# SAMD21_16X10_V2_schematic.net
KiCad netlist of a schematic drawn in Altium Designer
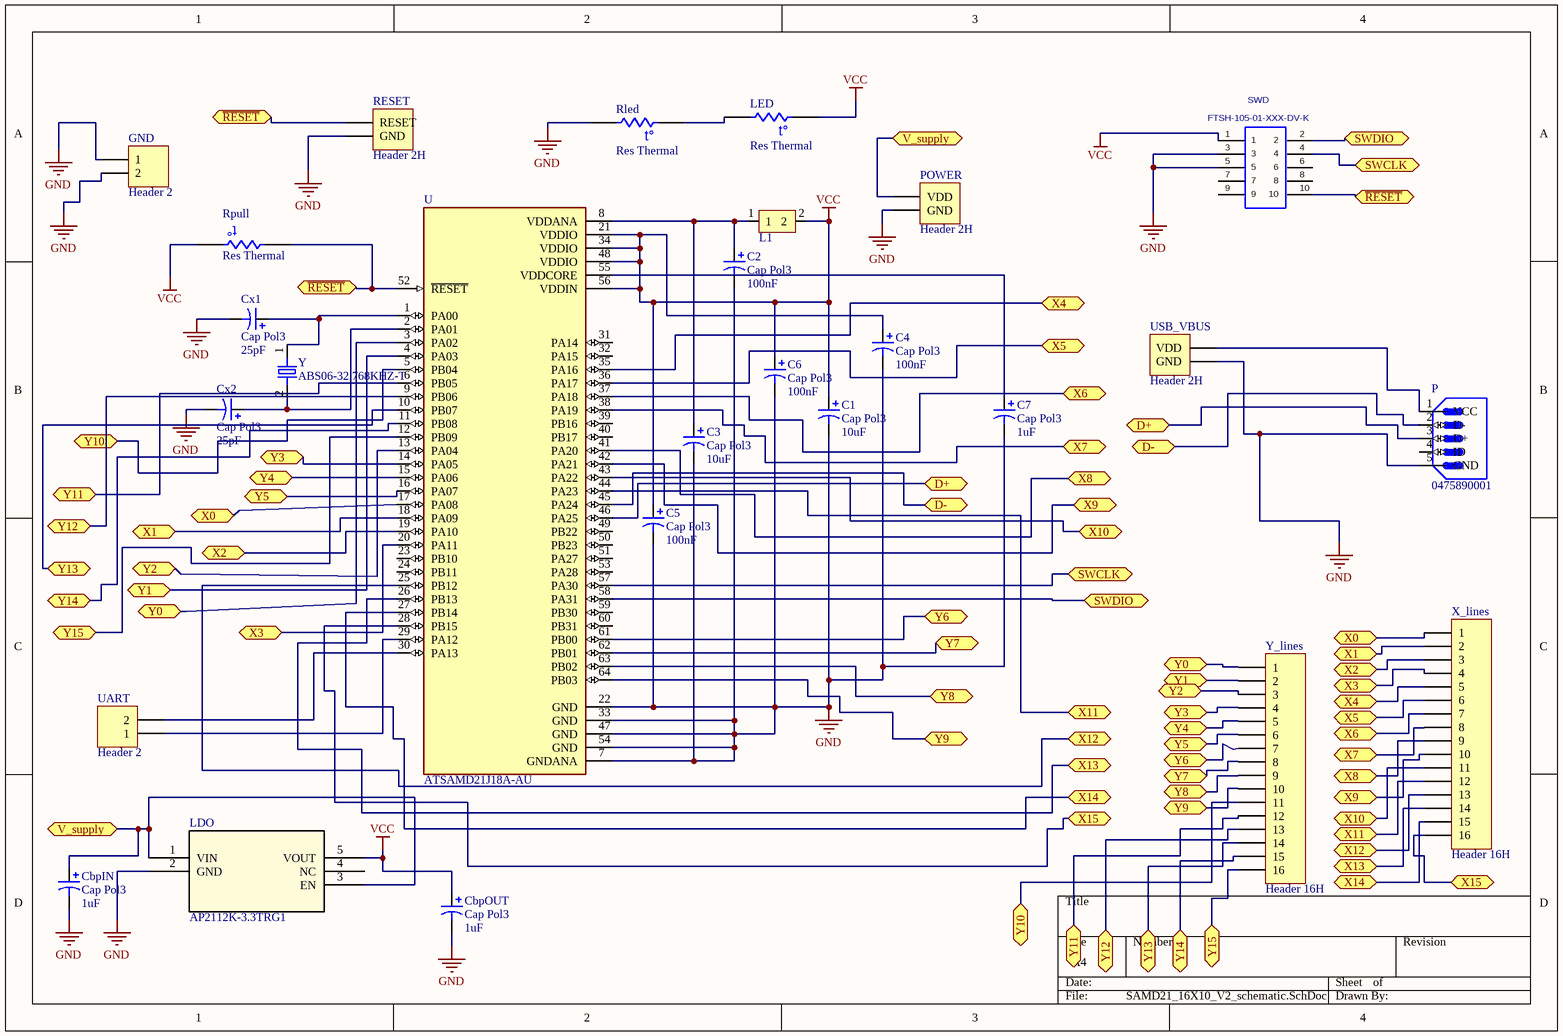
[diagram p0: SAMD21_16X10_V2_schematic.SchDoc]

(export (version "E")
  (design (tool "Eeschema 10.0.6"))
  (components
    (comp (ref "C1")
      (value "Cap Pol3")
      (footprint "C0805")
      (description "Polarized Capacitor (Surface Mount)")
      (fields (field (name "ALTIUM_VALUE") "10uF") (field (name "PUBLISHER") "Altium Limited"))
      (libsource (lib "Miscellaneous Devices") (part "Cap Pol3"))
    )
    (comp (ref "C2")
      (value "Cap Pol3")
      (footprint "C0805")
      (description "Polarized Capacitor (Surface Mount)")
      (fields (field (name "ALTIUM_VALUE") "100nF") (field (name "PUBLISHER") "Altium Limited"))
      (libsource (lib "Miscellaneous Devices") (part "Cap Pol3"))
    )
    (comp (ref "C3")
      (value "Cap Pol3")
      (footprint "C0805")
      (description "Polarized Capacitor (Surface Mount)")
      (fields (field (name "ALTIUM_VALUE") "10uF") (field (name "PUBLISHER") "Altium Limited"))
      (libsource (lib "Miscellaneous Devices") (part "Cap Pol3"))
    )
    (comp (ref "C4")
      (value "Cap Pol3")
      (footprint "C0805")
      (description "Polarized Capacitor (Surface Mount)")
      (fields (field (name "ALTIUM_VALUE") "100nF") (field (name "PUBLISHER") "Altium Limited"))
      (libsource (lib "Miscellaneous Devices") (part "Cap Pol3"))
    )
    (comp (ref "C5")
      (value "Cap Pol3")
      (footprint "C0805")
      (description "Polarized Capacitor (Surface Mount)")
      (fields (field (name "ALTIUM_VALUE") "100nF") (field (name "PUBLISHER") "Altium Limited"))
      (libsource (lib "Miscellaneous Devices") (part "Cap Pol3"))
    )
    (comp (ref "C6")
      (value "Cap Pol3")
      (footprint "C0805")
      (description "Polarized Capacitor (Surface Mount)")
      (fields (field (name "ALTIUM_VALUE") "100nF") (field (name "PUBLISHER") "Altium Limited"))
      (libsource (lib "Miscellaneous Devices") (part "Cap Pol3"))
    )
    (comp (ref "C7")
      (value "Cap Pol3")
      (footprint "C0805")
      (description "Polarized Capacitor (Surface Mount)")
      (fields (field (name "ALTIUM_VALUE") "1uF") (field (name "PUBLISHER") "Altium Limited"))
      (libsource (lib "Miscellaneous Devices") (part "Cap Pol3"))
    )
    (comp (ref "CbpIN")
      (value "Cap Pol3")
      (footprint "C0805")
      (description "Polarized Capacitor (Surface Mount)")
      (fields (field (name "ALTIUM_VALUE") "1uF") (field (name "PUBLISHER") "Altium Limited"))
      (libsource (lib "Miscellaneous Devices") (part "Cap Pol3"))
    )
    (comp (ref "CbpOUT")
      (value "Cap Pol3")
      (footprint "C0805")
      (description "Polarized Capacitor (Surface Mount)")
      (fields (field (name "ALTIUM_VALUE") "1uF") (field (name "PUBLISHER") "Altium Limited"))
      (libsource (lib "Miscellaneous Devices") (part "Cap Pol3"))
    )
    (comp (ref "Cx1")
      (value "Cap Pol3")
      (footprint "C0805")
      (description "Polarized Capacitor (Surface Mount)")
      (fields (field (name "ALTIUM_VALUE") "25pF") (field (name "PUBLISHER") "Altium Limited"))
      (libsource (lib "Miscellaneous Devices") (part "Cap Pol3"))
    )
    (comp (ref "Cx2")
      (value "Cap Pol3")
      (footprint "C0805")
      (description "Polarized Capacitor (Surface Mount)")
      (fields (field (name "ALTIUM_VALUE") "25pF") (field (name "PUBLISHER") "Altium Limited"))
      (libsource (lib "Miscellaneous Devices") (part "Cap Pol3"))
    )
    (comp (ref "GND")
      (value "Header 2")
      (footprint "HDR1X2")
      (description "Header, 2-Pin")
      (fields (field (name "PUBLISHER") "Altium Limited"))
      (libsource (lib "Miscellaneous Connectors") (part "Header 2"))
    )
    (comp (ref "L1")
      (value "SRP4012TA-100M")
      (footprint "Inductor")
      (description "Inductor")
      (libsource (lib "SRP4012TA") (part "SRP4012TA-100M"))
    )
    (comp (ref "LDO")
      (value "AP2112K-3.3TRG1")
      (footprint "SOT_RG1_DIO")
      (description "No Description Available")
      (fields (field (name "COPYRIGHT") "Copyright (C) 2018 Accelerated Designs. All rights reserved"))
      (libsource (lib "2020-09-03_20-14-04") (part "AP2112K-3.3TRG1"))
    )
    (comp (ref "LED")
      (value "Res Thermal")
      (footprint "6-0805_N")
      (description "Thermistor")
      (fields (field (name "PUBLISHER") "Altium Limited"))
      (libsource (lib "Miscellaneous Devices") (part "Res Thermal"))
    )
    (comp (ref "P")
      (value "0475890001")
      (footprint "MOLEX_0475890001")
      (description "USB - micro AB Receptacle Connector 5 Position Surface Mount, Right Angle; Through Hole")
      (fields (field (name "DIGI-KEY_PART_NUMBER") "WM17143CT-ND") (field (name "MF") "Molex"))
      (libsource (lib "0475890001") (part "0475890001"))
    )
    (comp (ref "POWER")
      (value "Header 2H")
      (footprint "HDR1X2H")
      (description "Header, 2-Pin, Right Angle")
      (fields (field (name "PUBLISHER") "Altium Limited"))
      (libsource (lib "") (part "Header 2H_1"))
    )
    (comp (ref "RESET")
      (value "Header 2H")
      (footprint "HDR1X2H")
      (description "Header, 2-Pin, Right Angle")
      (fields (field (name "PUBLISHER") "Altium Limited"))
      (libsource (lib "") (part "Header 2H_1"))
    )
    (comp (ref "Rled")
      (value "Res Thermal")
      (footprint "6-0805_N")
      (description "Thermistor")
      (fields (field (name "PUBLISHER") "Altium Limited"))
      (libsource (lib "Miscellaneous Devices") (part "Res Thermal"))
    )
    (comp (ref "Rpull")
      (value "Res Thermal")
      (footprint "6-0805_N")
      (description "Thermistor")
      (fields (field (name "PUBLISHER") "Altium Limited"))
      (libsource (lib "Miscellaneous Devices") (part "Res Thermal"))
    )
    (comp (ref "SWD")
      (value "FTSH-105-01-XXX-DV-K")
      (footprint "FTSH-105-01-XXX-DV-K")
      (description "TERMINAL STRIP, .050\"(1.27mm) PITCH, 10 PINS, KEYED")
      (fields (field (name "MANUFACTURER") "SAMTEC") (field (name "CREATED") "November 30, 2016 - Wendy Xin"))
      (libsource (lib "FTSH-105-01-XXX-DV-K--Symbol-Altium-44987") (part "FTSH-105-01-XXX-DV-K"))
    )
    (comp (ref "U")
      (value "ATSAMD21J18A-AU")
      (footprint "QFP80P1600X1600X120-64N")
      (description "ARMÂ® CortexÂ®-M0+ SAM D21J Microcontroller IC 32-Bit 48MHz 256KB _256K x 8_ FLASH 64-TQFP _10x10_")
      (fields (field (name "MF") "Microchip"))
      (libsource (lib "ATSAMD21J18A-AU") (part "ATSAMD21J18A-AU"))
    )
    (comp (ref "UART")
      (value "Header 2")
      (footprint "HDR1X2")
      (description "Header, 2-Pin")
      (fields (field (name "PUBLISHER") "Altium Limited"))
      (libsource (lib "") (part "Header 2_1"))
    )
    (comp (ref "USB_VBUS")
      (value "Header 2H")
      (footprint "HDR1X2H")
      (description "Header, 2-Pin, Right Angle")
      (fields (field (name "PUBLISHER") "Altium Limited"))
      (libsource (lib "Miscellaneous Connectors") (part "Header 2H"))
    )
    (comp (ref "X_lines")
      (value "Header 16H")
      (footprint "HDR1X16H")
      (description "Header, 16-Pin, Right Angle")
      (fields (field (name "PUBLISHER") "Altium Limited"))
      (libsource (lib "Miscellaneous Connectors") (part "Header 16H"))
    )
    (comp (ref "Y")
      (value "ABS06-32.768KHZ-T")
      (footprint "XTAL_ABS06-32.768KHZ-T")
      (description "32.768kHz Â±20ppm Crystal 12.5pF 90 kOhms 2-SMD, No Lead")
      (fields (field (name "MF") "Abracon"))
      (libsource (lib "ABS06-32.768KHZ-T") (part "ABS06-32.768KHZ-T"))
    )
    (comp (ref "Y_lines")
      (value "Header 16H")
      (footprint "HDR1X16H")
      (description "Header, 16-Pin, Right Angle")
      (fields (field (name "PUBLISHER") "Altium Limited"))
      (libsource (lib "Miscellaneous Connectors") (part "Header 16H"))
    )
  )
  (nets
    (net (code "1") (name "/D+") (class "Default")
      (node (ref "P") (pin "3") (pinfunction "D+_3") (pintype "bidirectional"))
      (node (ref "U") (pin "46") (pinfunction "PA25_46") (pintype "bidirectional"))
    )
    (net (code "2") (name "/D-") (class "Default")
      (node (ref "P") (pin "2") (pinfunction "D-_2") (pintype "bidirectional"))
      (node (ref "U") (pin "45") (pinfunction "PA24_45") (pintype "bidirectional"))
    )
    (net (code "3") (name "/SWCLK") (class "Default")
      (node (ref "SWD") (pin "4") (pinfunction "4_4") (pintype "passive"))
      (node (ref "U") (pin "57") (pinfunction "PA30_57") (pintype "bidirectional"))
    )
    (net (code "4") (name "/SWDIO") (class "Default")
      (node (ref "SWD") (pin "2") (pinfunction "2_2") (pintype "passive"))
      (node (ref "U") (pin "58") (pinfunction "PA31_58") (pintype "bidirectional"))
    )
    (net (code "5") (name "/V_supply") (class "Default")
      (node (ref "CbpIN") (pin "1") (pinfunction "1_1") (pintype "passive"))
      (node (ref "LDO") (pin "1") (pinfunction "VIN_1") (pintype "passive"))
      (node (ref "LDO") (pin "3") (pinfunction "EN_3") (pintype "passive"))
      (node (ref "POWER") (pin "1") (pinfunction "RESET_1") (pintype "passive"))
    )
    (net (code "6") (name "/X0") (class "Default")
      (node (ref "U") (pin "17") (pinfunction "PA08_17") (pintype "bidirectional"))
      (node (ref "X_lines") (pin "1") (pinfunction "1_1") (pintype "passive"))
    )
    (net (code "7") (name "/X1") (class "Default")
      (node (ref "U") (pin "18") (pinfunction "PA09_18") (pintype "bidirectional"))
      (node (ref "X_lines") (pin "2") (pinfunction "2_2") (pintype "passive"))
    )
    (net (code "8") (name "/X2") (class "Default")
      (node (ref "U") (pin "19") (pinfunction "PA10_19") (pintype "bidirectional"))
      (node (ref "X_lines") (pin "3") (pinfunction "3_3") (pintype "passive"))
    )
    (net (code "9") (name "/X3") (class "Default")
      (node (ref "U") (pin "20") (pinfunction "PA11_20") (pintype "bidirectional"))
      (node (ref "X_lines") (pin "4") (pinfunction "4_4") (pintype "passive"))
    )
    (net (code "10") (name "/X4") (class "Default")
      (node (ref "U") (pin "35") (pinfunction "PA16_35") (pintype "bidirectional"))
      (node (ref "X_lines") (pin "5") (pinfunction "5_5") (pintype "passive"))
    )
    (net (code "11") (name "/X5") (class "Default")
      (node (ref "U") (pin "36") (pinfunction "PA17_36") (pintype "bidirectional"))
      (node (ref "X_lines") (pin "6") (pinfunction "6_6") (pintype "passive"))
    )
    (net (code "12") (name "/X6") (class "Default")
      (node (ref "U") (pin "37") (pinfunction "PA18_37") (pintype "bidirectional"))
      (node (ref "X_lines") (pin "7") (pinfunction "7_7") (pintype "passive"))
    )
    (net (code "13") (name "/X7") (class "Default")
      (node (ref "U") (pin "38") (pinfunction "PA19_38") (pintype "bidirectional"))
      (node (ref "X_lines") (pin "8") (pinfunction "8_8") (pintype "passive"))
    )
    (net (code "14") (name "/X8") (class "Default")
      (node (ref "U") (pin "41") (pinfunction "PA20_41") (pintype "bidirectional"))
      (node (ref "X_lines") (pin "9") (pinfunction "9_9") (pintype "passive"))
    )
    (net (code "15") (name "/X9") (class "Default")
      (node (ref "U") (pin "42") (pinfunction "PA21_42") (pintype "bidirectional"))
      (node (ref "X_lines") (pin "10") (pinfunction "10_10") (pintype "passive"))
    )
    (net (code "16") (name "/X10") (class "Default")
      (node (ref "U") (pin "43") (pinfunction "PA22_43") (pintype "bidirectional"))
      (node (ref "X_lines") (pin "11") (pinfunction "11_11") (pintype "passive"))
    )
    (net (code "17") (name "/X11") (class "Default")
      (node (ref "U") (pin "44") (pinfunction "PA23_44") (pintype "bidirectional"))
      (node (ref "X_lines") (pin "12") (pinfunction "12_12") (pintype "passive"))
    )
    (net (code "18") (name "/X12") (class "Default")
      (node (ref "U") (pin "25") (pinfunction "PB12_25") (pintype "bidirectional"))
      (node (ref "X_lines") (pin "13") (pinfunction "13_13") (pintype "passive"))
    )
    (net (code "19") (name "/X13") (class "Default")
      (node (ref "U") (pin "26") (pinfunction "PB13_26") (pintype "bidirectional"))
      (node (ref "X_lines") (pin "14") (pinfunction "14_14") (pintype "passive"))
    )
    (net (code "20") (name "/X14") (class "Default")
      (node (ref "U") (pin "27") (pinfunction "PB14_27") (pintype "bidirectional"))
      (node (ref "X_lines") (pin "15") (pinfunction "15_15") (pintype "passive"))
    )
    (net (code "21") (name "/X15") (class "Default")
      (node (ref "U") (pin "28") (pinfunction "PB15_28") (pintype "bidirectional"))
      (node (ref "X_lines") (pin "16") (pinfunction "16_16") (pintype "passive"))
    )
    (net (code "22") (name "/Y0") (class "Default")
      (node (ref "U") (pin "3") (pinfunction "PA02_3") (pintype "bidirectional"))
      (node (ref "Y_lines") (pin "1") (pinfunction "1_1") (pintype "passive"))
    )
    (net (code "23") (name "/Y1") (class "Default")
      (node (ref "U") (pin "4") (pinfunction "PA03_4") (pintype "bidirectional"))
      (node (ref "Y_lines") (pin "2") (pinfunction "2_2") (pintype "passive"))
    )
    (net (code "24") (name "/Y2") (class "Default")
      (node (ref "U") (pin "13") (pinfunction "PA04_13") (pintype "bidirectional"))
      (node (ref "Y_lines") (pin "3") (pinfunction "3_3") (pintype "passive"))
    )
    (net (code "25") (name "/Y3") (class "Default")
      (node (ref "U") (pin "14") (pinfunction "PA05_14") (pintype "bidirectional"))
      (node (ref "Y_lines") (pin "4") (pinfunction "4_4") (pintype "passive"))
    )
    (net (code "26") (name "/Y4") (class "Default")
      (node (ref "U") (pin "15") (pinfunction "PA06_15") (pintype "bidirectional"))
      (node (ref "Y_lines") (pin "5") (pinfunction "5_5") (pintype "passive"))
    )
    (net (code "27") (name "/Y5") (class "Default")
      (node (ref "U") (pin "16") (pinfunction "PA07_16") (pintype "bidirectional"))
      (node (ref "Y_lines") (pin "6") (pinfunction "6_6") (pintype "passive"))
    )
    (net (code "28") (name "/Y6") (class "Default")
      (node (ref "U") (pin "61") (pinfunction "PB00_61") (pintype "bidirectional"))
      (node (ref "Y_lines") (pin "7") (pinfunction "7_7") (pintype "passive"))
    )
    (net (code "29") (name "/Y7") (class "Default")
      (node (ref "U") (pin "62") (pinfunction "PB01_62") (pintype "bidirectional"))
      (node (ref "Y_lines") (pin "8") (pinfunction "8_8") (pintype "passive"))
    )
    (net (code "30") (name "/Y8") (class "Default")
      (node (ref "U") (pin "63") (pinfunction "PB02_63") (pintype "bidirectional"))
      (node (ref "Y_lines") (pin "9") (pinfunction "9_9") (pintype "passive"))
    )
    (net (code "31") (name "/Y9") (class "Default")
      (node (ref "U") (pin "64") (pinfunction "PB03_64") (pintype "bidirectional"))
      (node (ref "Y_lines") (pin "10") (pinfunction "10_10") (pintype "passive"))
    )
    (net (code "32") (name "/Y10") (class "Default")
      (node (ref "U") (pin "5") (pinfunction "PB04_5") (pintype "bidirectional"))
      (node (ref "Y_lines") (pin "11") (pinfunction "11_11") (pintype "passive"))
    )
    (net (code "33") (name "/Y11") (class "Default")
      (node (ref "U") (pin "6") (pinfunction "PB05_6") (pintype "bidirectional"))
      (node (ref "Y_lines") (pin "12") (pinfunction "12_12") (pintype "passive"))
    )
    (net (code "34") (name "/Y12") (class "Default")
      (node (ref "U") (pin "9") (pinfunction "PB06_9") (pintype "bidirectional"))
      (node (ref "Y_lines") (pin "13") (pinfunction "13_13") (pintype "passive"))
    )
    (net (code "35") (name "/Y13") (class "Default")
      (node (ref "U") (pin "10") (pinfunction "PB07_10") (pintype "bidirectional"))
      (node (ref "Y_lines") (pin "14") (pinfunction "14_14") (pintype "passive"))
    )
    (net (code "36") (name "/Y14") (class "Default")
      (node (ref "U") (pin "11") (pinfunction "PB08_11") (pintype "bidirectional"))
      (node (ref "Y_lines") (pin "15") (pinfunction "15_15") (pintype "passive"))
    )
    (net (code "37") (name "/Y15") (class "Default")
      (node (ref "U") (pin "12") (pinfunction "PB09_12") (pintype "bidirectional"))
      (node (ref "Y_lines") (pin "16") (pinfunction "16_16") (pintype "passive"))
    )
    (net (code "38") (name "/~{RESET}") (class "Default")
      (node (ref "RESET") (pin "1") (pinfunction "RESET_1") (pintype "passive"))
      (node (ref "Rpull") (pin "2") (pinfunction "2_2") (pintype "passive"))
      (node (ref "SWD") (pin "10") (pinfunction "10_10") (pintype "passive"))
      (node (ref "U") (pin "52") (pinfunction "~{RESET}_52") (pintype "input"))
    )
    (net (code "39") (name "GND") (class "Default")
      (node (ref "C1") (pin "2") (pinfunction "2_2") (pintype "passive"))
      (node (ref "C2") (pin "2") (pinfunction "2_2") (pintype "passive"))
      (node (ref "C3") (pin "2") (pinfunction "2_2") (pintype "passive"))
      (node (ref "C4") (pin "2") (pinfunction "2_2") (pintype "passive"))
      (node (ref "C5") (pin "2") (pinfunction "2_2") (pintype "passive"))
      (node (ref "C6") (pin "2") (pinfunction "2_2") (pintype "passive"))
      (node (ref "C7") (pin "2") (pinfunction "2_2") (pintype "passive"))
      (node (ref "CbpIN") (pin "2") (pinfunction "2_2") (pintype "passive"))
      (node (ref "CbpOUT") (pin "2") (pinfunction "2_2") (pintype "passive"))
      (node (ref "Cx1") (pin "2") (pinfunction "2_2") (pintype "passive"))
      (node (ref "Cx2") (pin "2") (pinfunction "2_2") (pintype "passive"))
      (node (ref "GND") (pin "1") (pinfunction "1_1") (pintype "passive"))
      (node (ref "GND") (pin "2") (pinfunction "2_2") (pintype "passive"))
      (node (ref "LDO") (pin "2") (pinfunction "GND_2") (pintype "passive"))
      (node (ref "P") (pin "5") (pinfunction "GND_5") (pintype "power_in"))
      (node (ref "POWER") (pin "2") (pinfunction "GND_2") (pintype "passive"))
      (node (ref "RESET") (pin "2") (pinfunction "GND_2") (pintype "passive"))
      (node (ref "Rled") (pin "2") (pinfunction "2_2") (pintype "passive"))
      (node (ref "SWD") (pin "3") (pinfunction "3_3") (pintype "passive"))
      (node (ref "SWD") (pin "5") (pinfunction "5_5") (pintype "passive"))
      (node (ref "U") (pin "22") (pinfunction "GND_22") (pintype "power_in"))
      (node (ref "U") (pin "33") (pinfunction "GND_33") (pintype "power_in"))
      (node (ref "U") (pin "47") (pinfunction "GND_47") (pintype "power_in"))
      (node (ref "U") (pin "54") (pinfunction "GND_54") (pintype "power_in"))
      (node (ref "U") (pin "7") (pinfunction "GNDANA_7") (pintype "power_in"))
      (node (ref "USB_VBUS") (pin "1") (pinfunction "GND_1") (pintype "passive"))
    )
    (net (code "40") (name "Net-(LED-Pad2)") (class "Default")
      (node (ref "LED") (pin "2") (pinfunction "2_2") (pintype "passive"))
      (node (ref "Rled") (pin "1") (pinfunction "1_1") (pintype "passive"))
    )
    (net (code "41") (name "Net-(P-VCC)") (class "Default")
      (node (ref "P") (pin "1") (pinfunction "VCC_1") (pintype "power_in"))
      (node (ref "USB_VBUS") (pin "2") (pinfunction "VDD_2") (pintype "passive"))
    )
    (net (code "42") (name "Net-(U-PA00)") (class "Default")
      (node (ref "Cx1") (pin "1") (pinfunction "1_1") (pintype "passive"))
      (node (ref "U") (pin "1") (pinfunction "PA00_1") (pintype "bidirectional"))
      (node (ref "Y") (pin "1") (pinfunction "1_1") (pintype "passive"))
    )
    (net (code "43") (name "Net-(U-PA01)") (class "Default")
      (node (ref "Cx2") (pin "1") (pinfunction "1_1") (pintype "passive"))
      (node (ref "U") (pin "2") (pinfunction "PA01_2") (pintype "bidirectional"))
      (node (ref "Y") (pin "2") (pinfunction "2_2") (pintype "passive"))
    )
    (net (code "44") (name "Net-(U-PA12)") (class "Default")
      (node (ref "U") (pin "29") (pinfunction "PA12_29") (pintype "bidirectional"))
      (node (ref "UART") (pin "1") (pinfunction "1_1") (pintype "passive"))
    )
    (net (code "45") (name "Net-(U-PA13)") (class "Default")
      (node (ref "U") (pin "30") (pinfunction "PA13_30") (pintype "bidirectional"))
      (node (ref "UART") (pin "2") (pinfunction "2_2") (pintype "passive"))
    )
    (net (code "46") (name "Net-(U-VDDANA)") (class "Default")
      (node (ref "C2") (pin "1") (pinfunction "1_1") (pintype "passive"))
      (node (ref "C3") (pin "1") (pinfunction "1_1") (pintype "passive"))
      (node (ref "L1") (pin "1") (pinfunction "1_1") (pintype "passive"))
      (node (ref "U") (pin "8") (pinfunction "VDDANA_8") (pintype "power_in"))
    )
    (net (code "47") (name "Net-(U-VDDCORE)") (class "Default")
      (node (ref "C7") (pin "1") (pinfunction "1_1") (pintype "passive"))
      (node (ref "U") (pin "55") (pinfunction "VDDCORE_55") (pintype "power_in"))
    )
    (net (code "48") (name "VCC") (class "Default")
      (node (ref "C1") (pin "1") (pinfunction "1_1") (pintype "passive"))
      (node (ref "C4") (pin "1") (pinfunction "1_1") (pintype "passive"))
      (node (ref "C5") (pin "1") (pinfunction "1_1") (pintype "passive"))
      (node (ref "C6") (pin "1") (pinfunction "1_1") (pintype "passive"))
      (node (ref "CbpOUT") (pin "1") (pinfunction "1_1") (pintype "passive"))
      (node (ref "L1") (pin "2") (pinfunction "2_2") (pintype "passive"))
      (node (ref "LDO") (pin "5") (pinfunction "VOUT_5") (pintype "passive"))
      (node (ref "LED") (pin "1") (pinfunction "1_1") (pintype "passive"))
      (node (ref "Rpull") (pin "1") (pinfunction "1_1") (pintype "passive"))
      (node (ref "SWD") (pin "1") (pinfunction "1_1") (pintype "passive"))
      (node (ref "U") (pin "21") (pinfunction "VDDIO_21") (pintype "power_in"))
      (node (ref "U") (pin "34") (pinfunction "VDDIO_34") (pintype "power_in"))
      (node (ref "U") (pin "48") (pinfunction "VDDIO_48") (pintype "power_in"))
      (node (ref "U") (pin "56") (pinfunction "VDDIN_56") (pintype "power_in"))
    )
    (net (code "49") (name "unconnected-(LDO-NC-Pad4)") (class "Default")
      (node (ref "LDO") (pin "4") (pinfunction "NC_4") (pintype "passive"))
    )
    (net (code "50") (name "unconnected-(P-ID-Pad4)") (class "Default")
      (node (ref "P") (pin "4") (pinfunction "ID_4") (pintype "bidirectional"))
    )
    (net (code "51") (name "unconnected-(SWD-Pad6)") (class "Default")
      (node (ref "SWD") (pin "6") (pinfunction "6_6") (pintype "passive"))
    )
    (net (code "52") (name "unconnected-(SWD-Pad7)") (class "Default")
      (node (ref "SWD") (pin "7") (pinfunction "7_7") (pintype "passive"))
    )
    (net (code "53") (name "unconnected-(SWD-Pad8)") (class "Default")
      (node (ref "SWD") (pin "8") (pinfunction "8_8") (pintype "passive"))
    )
    (net (code "54") (name "unconnected-(SWD-Pad9)") (class "Default")
      (node (ref "SWD") (pin "9") (pinfunction "9_9") (pintype "passive"))
    )
    (net (code "55") (name "unconnected-(U-PA14-Pad31)") (class "Default")
      (node (ref "U") (pin "31") (pinfunction "PA14_31") (pintype "bidirectional"))
    )
    (net (code "56") (name "unconnected-(U-PA15-Pad32)") (class "Default")
      (node (ref "U") (pin "32") (pinfunction "PA15_32") (pintype "bidirectional"))
    )
    (net (code "57") (name "unconnected-(U-PA27-Pad51)") (class "Default")
      (node (ref "U") (pin "51") (pinfunction "PA27_51") (pintype "bidirectional"))
    )
    (net (code "58") (name "unconnected-(U-PA28-Pad53)") (class "Default")
      (node (ref "U") (pin "53") (pinfunction "PA28_53") (pintype "bidirectional"))
    )
    (net (code "59") (name "unconnected-(U-PB10-Pad23)") (class "Default")
      (node (ref "U") (pin "23") (pinfunction "PB10_23") (pintype "bidirectional"))
    )
    (net (code "60") (name "unconnected-(U-PB11-Pad24)") (class "Default")
      (node (ref "U") (pin "24") (pinfunction "PB11_24") (pintype "bidirectional"))
    )
    (net (code "61") (name "unconnected-(U-PB16-Pad39)") (class "Default")
      (node (ref "U") (pin "39") (pinfunction "PB16_39") (pintype "bidirectional"))
    )
    (net (code "62") (name "unconnected-(U-PB17-Pad40)") (class "Default")
      (node (ref "U") (pin "40") (pinfunction "PB17_40") (pintype "bidirectional"))
    )
    (net (code "63") (name "unconnected-(U-PB22-Pad49)") (class "Default")
      (node (ref "U") (pin "49") (pinfunction "PB22_49") (pintype "bidirectional"))
    )
    (net (code "64") (name "unconnected-(U-PB23-Pad50)") (class "Default")
      (node (ref "U") (pin "50") (pinfunction "PB23_50") (pintype "bidirectional"))
    )
    (net (code "65") (name "unconnected-(U-PB30-Pad59)") (class "Default")
      (node (ref "U") (pin "59") (pinfunction "PB30_59") (pintype "bidirectional"))
    )
    (net (code "66") (name "unconnected-(U-PB31-Pad60)") (class "Default")
      (node (ref "U") (pin "60") (pinfunction "PB31_60") (pintype "bidirectional"))
    )
  )
)
